# 09_LMS2_RF.net
KiCad netlist of a schematic drawn in Altium Designer
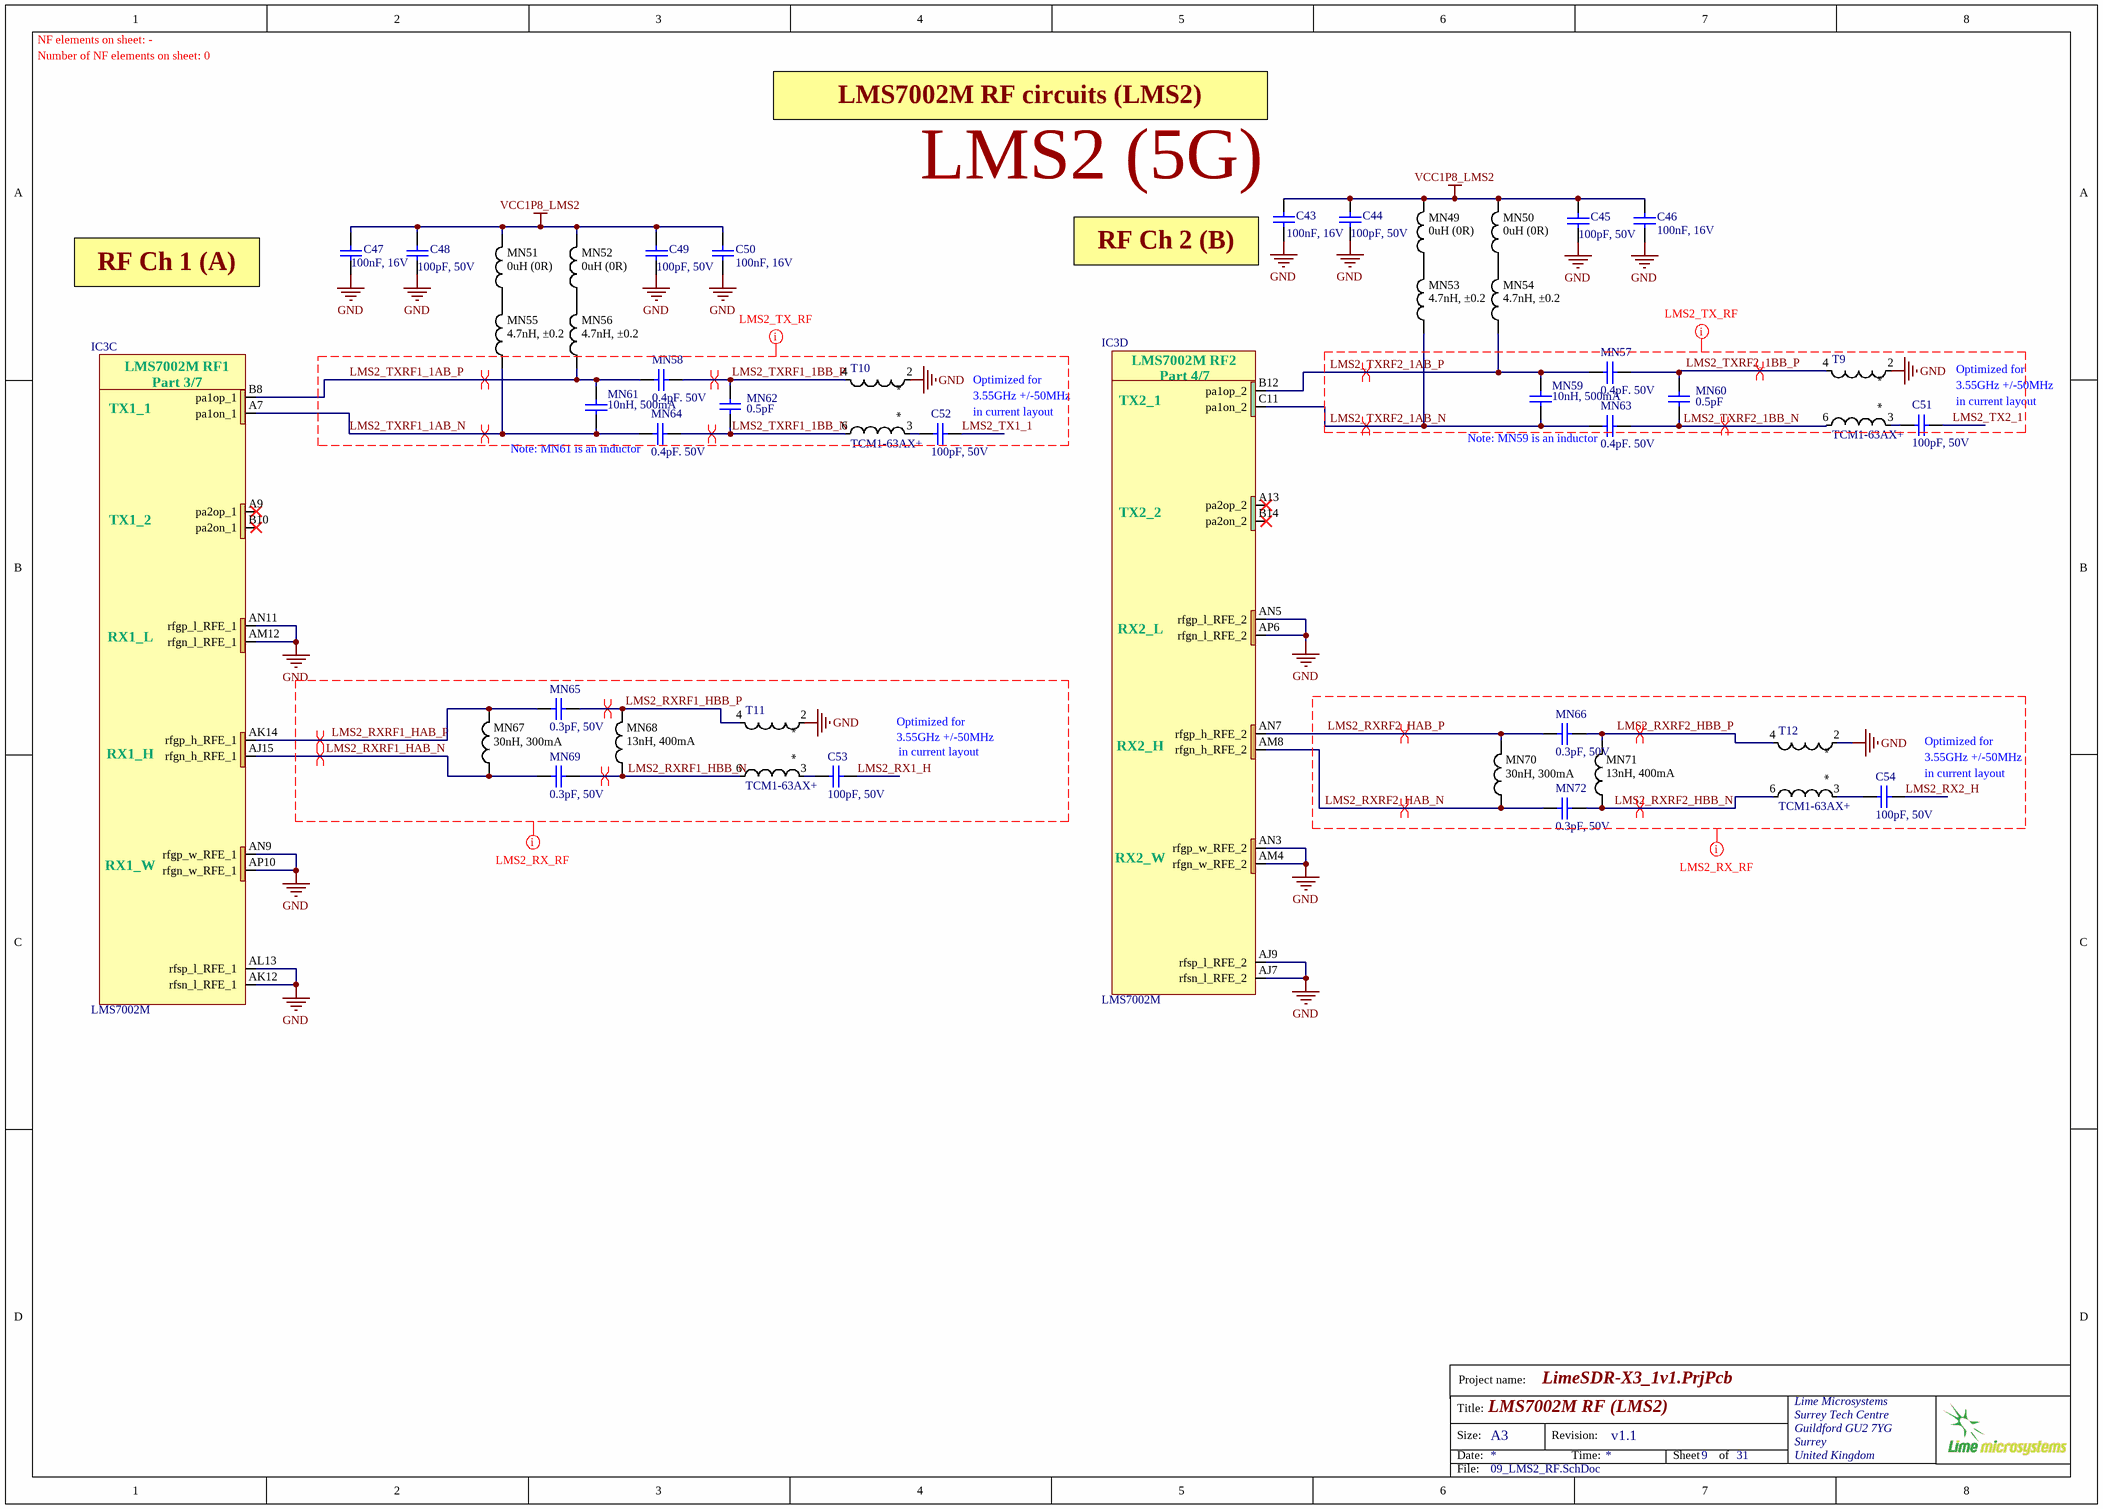
[diagram p0: 09_LMS2_RF.SchDoc]

(export (version "E")
  (design (tool "Eeschema 10.0.6"))
  (components
    (comp (ref "C43")
      (value "100nF, 16V")
      (footprint "CAP0402")
      (fields (field (name "MANUFACTURER") "Murata Electronics") (field (name "TOLERANCE") "10 %"))
      (libsource (lib "") (part "Cap_0402_3"))
    )
    (comp (ref "C44")
      (value "100pF, 50V")
      (footprint "CAP0402")
      (fields (field (name "MANUFACTURER") "Yageo") (field (name "TOLERANCE") "±5%"))
      (libsource (lib "LimeMicroAltiumLib_schLib") (part "Cap_0402"))
    )
    (comp (ref "C45")
      (value "100pF, 50V")
      (footprint "CAP0402")
      (fields (field (name "MANUFACTURER") "Yageo") (field (name "TOLERANCE") "±5%"))
      (libsource (lib "LimeMicroAltiumLib_schLib") (part "Cap_0402"))
    )
    (comp (ref "C46")
      (value "100nF, 16V")
      (footprint "CAP0402")
      (fields (field (name "MANUFACTURER") "Murata Electronics") (field (name "TOLERANCE") "10 %"))
      (libsource (lib "") (part "Cap_0402_3"))
    )
    (comp (ref "C47")
      (value "100nF, 16V")
      (footprint "CAP0402")
      (fields (field (name "MANUFACTURER") "Murata Electronics") (field (name "TOLERANCE") "10 %"))
      (libsource (lib "") (part "Cap_0402_5"))
    )
    (comp (ref "C48")
      (value "100pF, 50V")
      (footprint "CAP0402")
      (fields (field (name "MANUFACTURER") "Yageo") (field (name "TOLERANCE") "±5%"))
      (libsource (lib "LimeMicroAltiumLib_schLib") (part "Cap_0402"))
    )
    (comp (ref "C49")
      (value "100pF, 50V")
      (footprint "CAP0402")
      (fields (field (name "MANUFACTURER") "Yageo") (field (name "TOLERANCE") "±5%"))
      (libsource (lib "LimeMicroAltiumLib_schLib") (part "Cap_0402"))
    )
    (comp (ref "C50")
      (value "100nF, 16V")
      (footprint "CAP0402")
      (fields (field (name "MANUFACTURER") "Murata Electronics") (field (name "TOLERANCE") "10 %"))
      (libsource (lib "") (part "Cap_0402_5"))
    )
    (comp (ref "C51")
      (value "100pF, 50V")
      (footprint "CAP0402")
      (fields (field (name "TOLERANCE") "±5%") (field (name "MANUFACTURER") "Yageo"))
      (libsource (lib "") (part "Cap_0402_6"))
    )
    (comp (ref "C52")
      (value "100pF, 50V")
      (footprint "CAP0402")
      (fields (field (name "TOLERANCE") "±5%") (field (name "MANUFACTURER") "Yageo"))
      (libsource (lib "") (part "Cap_0402_6"))
    )
    (comp (ref "C53")
      (value "100pF, 50V")
      (footprint "CAP0402")
      (fields (field (name "TOLERANCE") "±5%") (field (name "MANUFACTURER") "Yageo"))
      (libsource (lib "") (part "Cap_0402_4"))
    )
    (comp (ref "C54")
      (value "100pF, 50V")
      (footprint "CAP0402")
      (fields (field (name "TOLERANCE") "±5%") (field (name "MANUFACTURER") "Yageo"))
      (libsource (lib "") (part "Cap_0402_4"))
    )
    (comp (ref "IC3")
      (value "LMS7002M")
      (footprint "LMS7002M_v5")
      (description "Schematic symbol revision 4. Default footprint - 0.31mm pad")
      (fields (field (name "MANUFACTURER") "Lime Microsystems"))
      (libsource (lib "LimeMicroAltiumLib_schLib_r04") (part "LMS7002Mr4"))
    )
    (comp (ref "MN49")
      (value "0uH (0R)")
      (footprint "RES0603")
      (fields
        (field (name "MANUFACTURER") "Panasonic Electronic Components")
        (field (name "MANUFACTURER PART NUMBER") "ERJ-3GEY0R00V")
        (field (name "TOLERANCE") "Jumper")
      )
      (libsource (lib "LimeMicroAltiumLib_schLib") (part "Inductor_0603"))
    )
    (comp (ref "MN50")
      (value "0uH (0R)")
      (footprint "RES0603")
      (fields
        (field (name "MANUFACTURER") "Panasonic Electronic Components")
        (field (name "MANUFACTURER PART NUMBER") "ERJ-3GEY0R00V")
        (field (name "TOLERANCE") "Jumper")
      )
      (libsource (lib "LimeMicroAltiumLib_schLib") (part "Inductor_0603"))
    )
    (comp (ref "MN51")
      (value "0uH (0R)")
      (footprint "RES0603")
      (fields
        (field (name "MANUFACTURER") "Panasonic Electronic Components")
        (field (name "MANUFACTURER PART NUMBER") "ERJ-3GEY0R00V")
        (field (name "TOLERANCE") "Jumper")
      )
      (libsource (lib "LimeMicroAltiumLib_schLib") (part "Inductor_0603"))
    )
    (comp (ref "MN52")
      (value "0uH (0R)")
      (footprint "RES0603")
      (fields
        (field (name "MANUFACTURER") "Panasonic Electronic Components")
        (field (name "MANUFACTURER PART NUMBER") "ERJ-3GEY0R00V")
        (field (name "TOLERANCE") "Jumper")
      )
      (libsource (lib "LimeMicroAltiumLib_schLib") (part "Inductor_0603"))
    )
    (comp (ref "MN53")
      (value "4.7nH, ±0.2")
      (footprint "RES0402")
      (fields (field (name "MANUFACTURER") "Murata"))
      (libsource (lib "LimeMicroAltiumLib_schLib") (part "Inductor_0603"))
    )
    (comp (ref "MN54")
      (value "4.7nH, ±0.2")
      (footprint "RES0402")
      (fields (field (name "MANUFACTURER") "Murata"))
      (libsource (lib "LimeMicroAltiumLib_schLib") (part "Inductor_0603"))
    )
    (comp (ref "MN55")
      (value "4.7nH, ±0.2")
      (footprint "RES0402")
      (fields (field (name "MANUFACTURER") "Murata"))
      (libsource (lib "LimeMicroAltiumLib_schLib") (part "Inductor_0603"))
    )
    (comp (ref "MN56")
      (value "4.7nH, ±0.2")
      (footprint "RES0402")
      (fields (field (name "MANUFACTURER") "Murata"))
      (libsource (lib "LimeMicroAltiumLib_schLib") (part "Inductor_0603"))
    )
    (comp (ref "MN57")
      (value "0.4pF. 50V")
      (footprint "CAP0402")
      (fields (field (name "MANUFACTURER") "Murata"))
      (libsource (lib "") (part "Cap_0402_2"))
    )
    (comp (ref "MN58")
      (value "0.4pF. 50V")
      (footprint "CAP0402")
      (fields (field (name "MANUFACTURER") "Murata"))
      (libsource (lib "") (part "Cap_0402_2"))
    )
    (comp (ref "MN59")
      (value "10nH, 500mA")
      (footprint "CAP0402")
      (fields (field (name "MANUFACTURER") "Murata") (field (name "TOLERANCE") "2%"))
      (libsource (lib "") (part "Cap_0402_1"))
    )
    (comp (ref "MN60")
      (value "0.5pF")
      (footprint "CAP0402")
      (fields (field (name "TOLERANCE") "±0.25pF") (field (name "MANUFACTURER") "Yageo"))
      (libsource (lib "") (part "Cap_0402_6"))
    )
    (comp (ref "MN61")
      (value "10nH, 500mA")
      (footprint "CAP0402")
      (fields (field (name "MANUFACTURER") "Murata") (field (name "TOLERANCE") "2%"))
      (libsource (lib "") (part "Cap_0402_1"))
    )
    (comp (ref "MN62")
      (value "0.5pF")
      (footprint "CAP0402")
      (fields (field (name "TOLERANCE") "±0.25pF") (field (name "MANUFACTURER") "Yageo"))
      (libsource (lib "") (part "Cap_0402_6"))
    )
    (comp (ref "MN63")
      (value "0.4pF. 50V")
      (footprint "CAP0402")
      (fields (field (name "MANUFACTURER") "Murata"))
      (libsource (lib "") (part "Cap_0402_7"))
    )
    (comp (ref "MN64")
      (value "0.4pF. 50V")
      (footprint "CAP0402")
      (fields (field (name "MANUFACTURER") "Murata"))
      (libsource (lib "") (part "Cap_0402_7"))
    )
    (comp (ref "MN65")
      (value "0.3pF, 50V")
      (footprint "CAP0402")
      (fields (field (name "MANUFACTURER") "Johanson"))
      (libsource (lib "") (part "Cap_0402_2"))
    )
    (comp (ref "MN66")
      (value "0.3pF, 50V")
      (footprint "CAP0402")
      (fields (field (name "MANUFACTURER") "Johanson"))
      (libsource (lib "") (part "Cap_0402_2"))
    )
    (comp (ref "MN67")
      (value "30nH, 300mA")
      (footprint "RES0402")
      (fields (field (name "MANUFACTURER") "TDK") (field (name "TOLERANCE") "5%"))
      (libsource (lib "") (part "Inductor_0603_1"))
    )
    (comp (ref "MN68")
      (value "13nH, 400mA")
      (footprint "RES0402")
      (fields (field (name "MANUFACTURER") "TDK") (field (name "TOLERANCE") "5%"))
      (libsource (lib "") (part "Inductor_0603_2"))
    )
    (comp (ref "MN69")
      (value "0.3pF, 50V")
      (footprint "CAP0402")
      (fields (field (name "MANUFACTURER") "Johanson"))
      (libsource (lib "") (part "Cap_0402_2"))
    )
    (comp (ref "MN70")
      (value "30nH, 300mA")
      (footprint "RES0402")
      (fields (field (name "MANUFACTURER") "TDK") (field (name "TOLERANCE") "5%"))
      (libsource (lib "") (part "Inductor_0603_1"))
    )
    (comp (ref "MN71")
      (value "13nH, 400mA")
      (footprint "RES0402")
      (fields (field (name "MANUFACTURER") "TDK") (field (name "TOLERANCE") "5%"))
      (libsource (lib "") (part "Inductor_0603_2"))
    )
    (comp (ref "MN72")
      (value "0.3pF, 50V")
      (footprint "CAP0402")
      (fields (field (name "MANUFACTURER") "Johanson"))
      (libsource (lib "") (part "Cap_0402_2"))
    )
    (comp (ref "T9")
      (value "TCM1-63AX+")
      (footprint "TCM1-63AX+_v2")
      (fields (field (name "MANUFACTURER") "Mini-circuits"))
      (libsource (lib "") (part "Balun_v2_1"))
    )
    (comp (ref "T10")
      (value "TCM1-63AX+")
      (footprint "TCM1-63AX+_v2")
      (fields (field (name "MANUFACTURER") "Mini-circuits"))
      (libsource (lib "") (part "Balun_v2_1"))
    )
    (comp (ref "T11")
      (value "TCM1-63AX+")
      (footprint "TCM1-63AX+_v2")
      (fields (field (name "MANUFACTURER") "Mini-circuits"))
      (libsource (lib "LimeMicroAltiumLib_schLib") (part "Balun_v2"))
    )
    (comp (ref "T12")
      (value "TCM1-63AX+")
      (footprint "TCM1-63AX+_v2")
      (fields (field (name "MANUFACTURER") "Mini-circuits"))
      (libsource (lib "LimeMicroAltiumLib_schLib") (part "Balun_v2"))
    )
  )
  (nets
    (net (code "1") (name "/LMS2_RX1_H") (class "Default")
      (node (ref "C53") (pin "1") (pinfunction "1_1") (pintype "passive"))
    )
    (net (code "2") (name "/LMS2_RX2_H") (class "Default")
      (node (ref "C54") (pin "1") (pinfunction "1_1") (pintype "passive"))
    )
    (net (code "3") (name "/LMS2_RXRF1_HAB_N") (class "Default")
      (node (ref "IC3") (pin "AJ15") (pinfunction "rfgn_h_RFE_1_AJ15") (pintype "passive"))
      (node (ref "MN67") (pin "1") (pinfunction "1_1") (pintype "passive"))
      (node (ref "MN69") (pin "2") (pinfunction "2_2") (pintype "passive"))
    )
    (net (code "4") (name "/LMS2_RXRF1_HAB_P") (class "Default")
      (node (ref "IC3") (pin "AK14") (pinfunction "rfgp_h_RFE_1_AK14") (pintype "passive"))
      (node (ref "MN65") (pin "2") (pinfunction "2_2") (pintype "passive"))
      (node (ref "MN67") (pin "2") (pinfunction "2_2") (pintype "passive"))
    )
    (net (code "5") (name "/LMS2_RXRF1_HBB_N") (class "Default")
      (node (ref "MN68") (pin "1") (pinfunction "1_1") (pintype "passive"))
      (node (ref "MN69") (pin "1") (pinfunction "1_1") (pintype "passive"))
      (node (ref "T11") (pin "6") (pinfunction "6_6") (pintype "passive"))
    )
    (net (code "6") (name "/LMS2_RXRF1_HBB_P") (class "Default")
      (node (ref "MN65") (pin "1") (pinfunction "1_1") (pintype "passive"))
      (node (ref "MN68") (pin "2") (pinfunction "2_2") (pintype "passive"))
      (node (ref "T11") (pin "4") (pinfunction "4_4") (pintype "passive"))
    )
    (net (code "7") (name "/LMS2_RXRF2_HAB_N") (class "Default")
      (node (ref "IC3") (pin "AM8") (pinfunction "rfgn_h_RFE_2_AM8") (pintype "passive"))
      (node (ref "MN70") (pin "1") (pinfunction "1_1") (pintype "passive"))
      (node (ref "MN72") (pin "2") (pinfunction "2_2") (pintype "passive"))
    )
    (net (code "8") (name "/LMS2_RXRF2_HAB_P") (class "Default")
      (node (ref "IC3") (pin "AN7") (pinfunction "rfgp_h_RFE_2_AN7") (pintype "passive"))
      (node (ref "MN66") (pin "2") (pinfunction "2_2") (pintype "passive"))
      (node (ref "MN70") (pin "2") (pinfunction "2_2") (pintype "passive"))
    )
    (net (code "9") (name "/LMS2_RXRF2_HBB_N") (class "Default")
      (node (ref "MN71") (pin "1") (pinfunction "1_1") (pintype "passive"))
      (node (ref "MN72") (pin "1") (pinfunction "1_1") (pintype "passive"))
      (node (ref "T12") (pin "6") (pinfunction "6_6") (pintype "passive"))
    )
    (net (code "10") (name "/LMS2_RXRF2_HBB_P") (class "Default")
      (node (ref "MN66") (pin "1") (pinfunction "1_1") (pintype "passive"))
      (node (ref "MN71") (pin "2") (pinfunction "2_2") (pintype "passive"))
      (node (ref "T12") (pin "4") (pinfunction "4_4") (pintype "passive"))
    )
    (net (code "11") (name "/LMS2_TX1_1") (class "Default")
      (node (ref "C52") (pin "1") (pinfunction "1_1") (pintype "passive"))
    )
    (net (code "12") (name "/LMS2_TX2_1") (class "Default")
      (node (ref "C51") (pin "1") (pinfunction "1_1") (pintype "passive"))
    )
    (net (code "13") (name "/LMS2_TXRF1_1AB_N") (class "Default")
      (node (ref "IC3") (pin "A7") (pinfunction "pa1on_1_A7") (pintype "passive"))
      (node (ref "MN55") (pin "1") (pinfunction "1_1") (pintype "passive"))
      (node (ref "MN61") (pin "2") (pinfunction "2_2") (pintype "passive"))
      (node (ref "MN64") (pin "2") (pinfunction "2_2") (pintype "passive"))
    )
    (net (code "14") (name "/LMS2_TXRF1_1AB_P") (class "Default")
      (node (ref "IC3") (pin "B8") (pinfunction "pa1op_1_B8") (pintype "passive"))
      (node (ref "MN56") (pin "1") (pinfunction "1_1") (pintype "passive"))
      (node (ref "MN58") (pin "2") (pinfunction "2_2") (pintype "passive"))
      (node (ref "MN61") (pin "1") (pinfunction "1_1") (pintype "passive"))
    )
    (net (code "15") (name "/LMS2_TXRF1_1BB_N") (class "Default")
      (node (ref "MN62") (pin "1") (pinfunction "1_1") (pintype "passive"))
      (node (ref "MN64") (pin "1") (pinfunction "1_1") (pintype "passive"))
      (node (ref "T10") (pin "6") (pinfunction "6_6") (pintype "passive"))
    )
    (net (code "16") (name "/LMS2_TXRF1_1BB_P") (class "Default")
      (node (ref "MN58") (pin "1") (pinfunction "1_1") (pintype "passive"))
      (node (ref "MN62") (pin "2") (pinfunction "2_2") (pintype "passive"))
      (node (ref "T10") (pin "4") (pinfunction "4_4") (pintype "passive"))
    )
    (net (code "17") (name "/LMS2_TXRF2_1AB_N") (class "Default")
      (node (ref "IC3") (pin "C11") (pinfunction "pa1on_2_C11") (pintype "passive"))
      (node (ref "MN53") (pin "1") (pinfunction "1_1") (pintype "passive"))
      (node (ref "MN59") (pin "2") (pinfunction "2_2") (pintype "passive"))
      (node (ref "MN63") (pin "2") (pinfunction "2_2") (pintype "passive"))
    )
    (net (code "18") (name "/LMS2_TXRF2_1AB_P") (class "Default")
      (node (ref "IC3") (pin "B12") (pinfunction "pa1op_2_B12") (pintype "passive"))
      (node (ref "MN54") (pin "1") (pinfunction "1_1") (pintype "passive"))
      (node (ref "MN57") (pin "2") (pinfunction "2_2") (pintype "passive"))
      (node (ref "MN59") (pin "1") (pinfunction "1_1") (pintype "passive"))
    )
    (net (code "19") (name "/LMS2_TXRF2_1BB_N") (class "Default")
      (node (ref "MN60") (pin "1") (pinfunction "1_1") (pintype "passive"))
      (node (ref "MN63") (pin "1") (pinfunction "1_1") (pintype "passive"))
      (node (ref "T9") (pin "6") (pinfunction "6_6") (pintype "passive"))
    )
    (net (code "20") (name "/LMS2_TXRF2_1BB_P") (class "Default")
      (node (ref "MN57") (pin "1") (pinfunction "1_1") (pintype "passive"))
      (node (ref "MN60") (pin "2") (pinfunction "2_2") (pintype "passive"))
      (node (ref "T9") (pin "4") (pinfunction "4_4") (pintype "passive"))
    )
    (net (code "21") (name "GND") (class "Default")
      (node (ref "C43") (pin "1") (pinfunction "1_1") (pintype "passive"))
      (node (ref "C44") (pin "1") (pinfunction "1_1") (pintype "passive"))
      (node (ref "C45") (pin "1") (pinfunction "1_1") (pintype "passive"))
      (node (ref "C46") (pin "1") (pinfunction "1_1") (pintype "passive"))
      (node (ref "C47") (pin "1") (pinfunction "1_1") (pintype "passive"))
      (node (ref "C48") (pin "1") (pinfunction "1_1") (pintype "passive"))
      (node (ref "C49") (pin "1") (pinfunction "1_1") (pintype "passive"))
      (node (ref "C50") (pin "1") (pinfunction "1_1") (pintype "passive"))
      (node (ref "IC3") (pin "AJ7") (pinfunction "rfsn_l_RFE_2_AJ7") (pintype "passive"))
      (node (ref "IC3") (pin "AJ9") (pinfunction "rfsp_l_RFE_2_AJ9") (pintype "passive"))
      (node (ref "IC3") (pin "AK12") (pinfunction "rfsn_l_RFE_1_AK12") (pintype "passive"))
      (node (ref "IC3") (pin "AL13") (pinfunction "rfsp_l_RFE_1_AL13") (pintype "passive"))
      (node (ref "IC3") (pin "AM12") (pinfunction "rfgn_l_RFE_1_AM12") (pintype "passive"))
      (node (ref "IC3") (pin "AM4") (pinfunction "rfgn_w_RFE_2_AM4") (pintype "passive"))
      (node (ref "IC3") (pin "AN11") (pinfunction "rfgp_l_RFE_1_AN11") (pintype "passive"))
      (node (ref "IC3") (pin "AN3") (pinfunction "rfgp_w_RFE_2_AN3") (pintype "passive"))
      (node (ref "IC3") (pin "AN5") (pinfunction "rfgp_l_RFE_2_AN5") (pintype "passive"))
      (node (ref "IC3") (pin "AN9") (pinfunction "rfgp_w_RFE_1_AN9") (pintype "passive"))
      (node (ref "IC3") (pin "AP10") (pinfunction "rfgn_w_RFE_1_AP10") (pintype "passive"))
      (node (ref "IC3") (pin "AP6") (pinfunction "rfgn_l_RFE_2_AP6") (pintype "passive"))
      (node (ref "T10") (pin "2") (pinfunction "2_2") (pintype "passive"))
      (node (ref "T11") (pin "2") (pinfunction "2_2") (pintype "passive"))
      (node (ref "T12") (pin "2") (pinfunction "2_2") (pintype "passive"))
      (node (ref "T9") (pin "2") (pinfunction "2_2") (pintype "passive"))
    )
    (net (code "22") (name "Net-(C51-Pad2)") (class "Default")
      (node (ref "C51") (pin "2") (pinfunction "2_2") (pintype "passive"))
      (node (ref "T9") (pin "3") (pinfunction "3_3") (pintype "passive"))
    )
    (net (code "23") (name "Net-(C52-Pad2)") (class "Default")
      (node (ref "C52") (pin "2") (pinfunction "2_2") (pintype "passive"))
      (node (ref "T10") (pin "3") (pinfunction "3_3") (pintype "passive"))
    )
    (net (code "24") (name "Net-(C53-Pad2)") (class "Default")
      (node (ref "C53") (pin "2") (pinfunction "2_2") (pintype "passive"))
      (node (ref "T11") (pin "3") (pinfunction "3_3") (pintype "passive"))
    )
    (net (code "25") (name "Net-(C54-Pad2)") (class "Default")
      (node (ref "C54") (pin "2") (pinfunction "2_2") (pintype "passive"))
      (node (ref "T12") (pin "3") (pinfunction "3_3") (pintype "passive"))
    )
    (net (code "26") (name "Net-(MN49-Pad1)") (class "Default")
      (node (ref "MN49") (pin "1") (pinfunction "1_1") (pintype "passive"))
      (node (ref "MN53") (pin "2") (pinfunction "2_2") (pintype "passive"))
    )
    (net (code "27") (name "Net-(MN50-Pad1)") (class "Default")
      (node (ref "MN50") (pin "1") (pinfunction "1_1") (pintype "passive"))
      (node (ref "MN54") (pin "2") (pinfunction "2_2") (pintype "passive"))
    )
    (net (code "28") (name "Net-(MN51-Pad1)") (class "Default")
      (node (ref "MN51") (pin "1") (pinfunction "1_1") (pintype "passive"))
      (node (ref "MN55") (pin "2") (pinfunction "2_2") (pintype "passive"))
    )
    (net (code "29") (name "Net-(MN52-Pad1)") (class "Default")
      (node (ref "MN52") (pin "1") (pinfunction "1_1") (pintype "passive"))
      (node (ref "MN56") (pin "2") (pinfunction "2_2") (pintype "passive"))
    )
    (net (code "30") (name "VCC1P8_LMS2") (class "Default")
      (node (ref "C43") (pin "2") (pinfunction "2_2") (pintype "passive"))
      (node (ref "C44") (pin "2") (pinfunction "2_2") (pintype "passive"))
      (node (ref "C45") (pin "2") (pinfunction "2_2") (pintype "passive"))
      (node (ref "C46") (pin "2") (pinfunction "2_2") (pintype "passive"))
      (node (ref "C47") (pin "2") (pinfunction "2_2") (pintype "passive"))
      (node (ref "C48") (pin "2") (pinfunction "2_2") (pintype "passive"))
      (node (ref "C49") (pin "2") (pinfunction "2_2") (pintype "passive"))
      (node (ref "C50") (pin "2") (pinfunction "2_2") (pintype "passive"))
      (node (ref "MN49") (pin "2") (pinfunction "2_2") (pintype "passive"))
      (node (ref "MN50") (pin "2") (pinfunction "2_2") (pintype "passive"))
      (node (ref "MN51") (pin "2") (pinfunction "2_2") (pintype "passive"))
      (node (ref "MN52") (pin "2") (pinfunction "2_2") (pintype "passive"))
    )
    (net (code "31") (name "unconnected-(IC3C-pa2on_1-PadB10)") (class "Default")
      (node (ref "IC3") (pin "B10") (pinfunction "pa2on_1_B10") (pintype "passive+no_connect"))
    )
    (net (code "32") (name "unconnected-(IC3C-pa2op_1-PadA9)") (class "Default")
      (node (ref "IC3") (pin "A9") (pinfunction "pa2op_1_A9") (pintype "passive+no_connect"))
    )
    (net (code "33") (name "unconnected-(IC3D-pa2on_2-PadB14)") (class "Default")
      (node (ref "IC3") (pin "B14") (pinfunction "pa2on_2_B14") (pintype "passive+no_connect"))
    )
    (net (code "34") (name "unconnected-(IC3D-pa2op_2-PadA13)") (class "Default")
      (node (ref "IC3") (pin "A13") (pinfunction "pa2op_2_A13") (pintype "passive+no_connect"))
    )
  )
)
